# raindrops.net
KiCad netlist of a schematic drawn in EAGLE
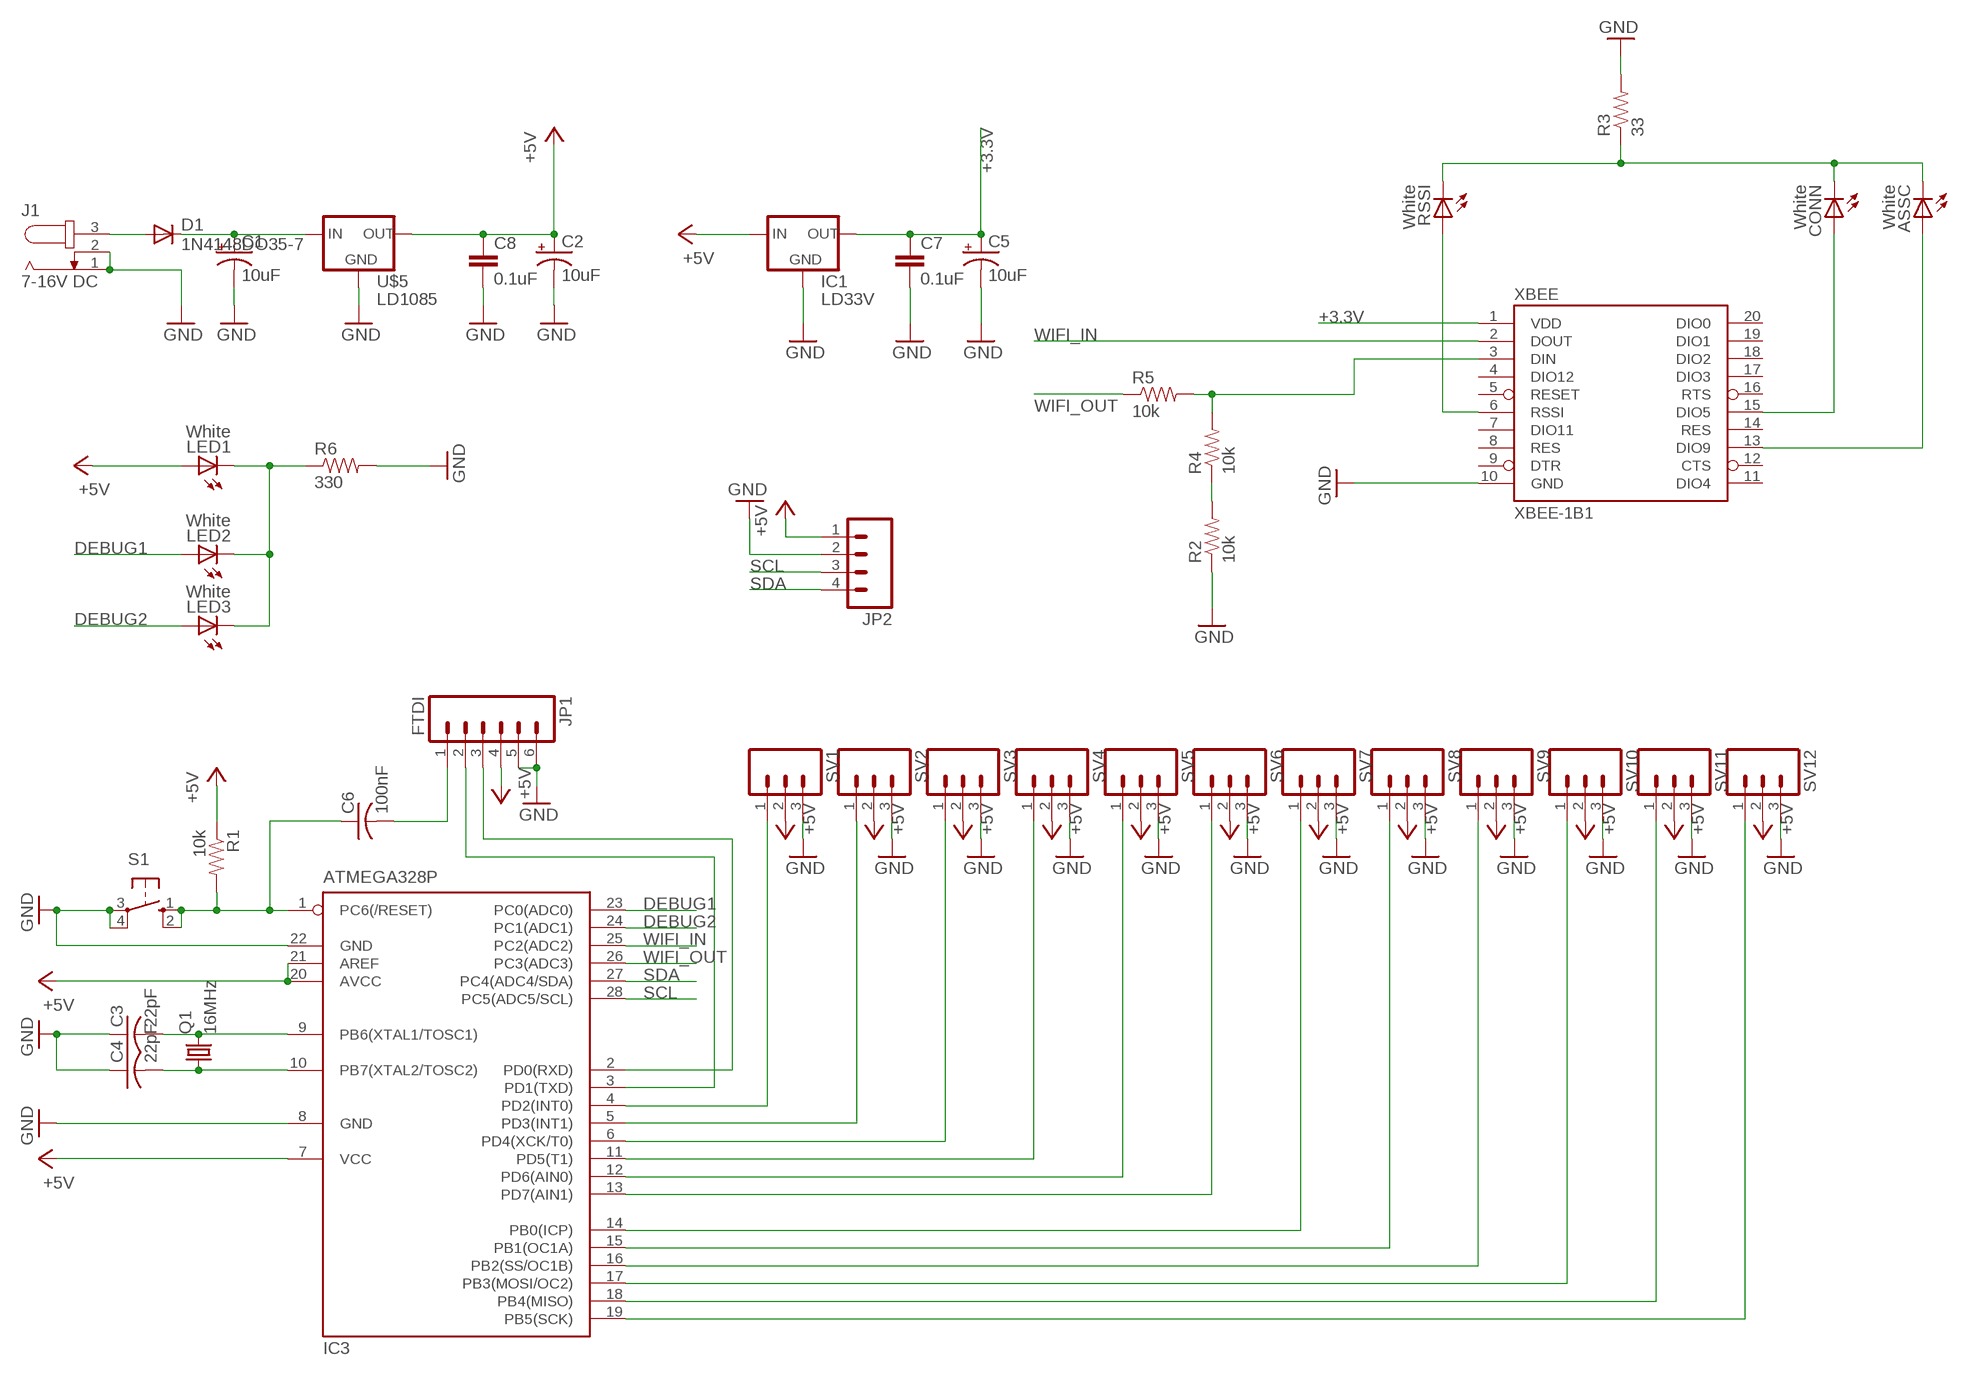
[diagram p0: schematic, sheet 1]

(export (version "E")
  (design (tool "Eeschema 10.0.6"))
  (components
    (comp (ref "ASSC")
      (value "White")
      (footprint "eagle-import:CHIPLED_0603")
      (libsource (lib "eagle-import") (part "LEDCHIPLED_0603"))
    )
    (comp (ref "C1")
      (value "10uF")
      (footprint "eagle-import:CPOL-RADIAL-10UF-25V")
      (libsource (lib "eagle-import") (part "CAP_POLPTH2"))
    )
    (comp (ref "C2")
      (value "10uF")
      (footprint "eagle-import:CPOL-RADIAL-10UF-25V")
      (libsource (lib "eagle-import") (part "CAP_POLPTH2"))
    )
    (comp (ref "C3")
      (value "22pF")
      (footprint "eagle-import:C025-025X050")
      (libsource (lib "eagle-import") (part "C-US025-025X050"))
    )
    (comp (ref "C4")
      (value "22pF")
      (footprint "eagle-import:C025-025X050")
      (libsource (lib "eagle-import") (part "C-US025-025X050"))
    )
    (comp (ref "C5")
      (value "10uF")
      (footprint "eagle-import:CPOL-RADIAL-10UF-25V")
      (libsource (lib "eagle-import") (part "CAP_POLPTH2"))
    )
    (comp (ref "C6")
      (value "100nF")
      (footprint "eagle-import:C025-025X050")
      (libsource (lib "eagle-import") (part "C-US025-025X050"))
    )
    (comp (ref "C7")
      (value "0.1uF")
      (footprint "eagle-import:0402-CAP")
      (libsource (lib "eagle-import") (part ".1UF-CER"))
    )
    (comp (ref "C8")
      (value "0.1uF")
      (footprint "eagle-import:0402-CAP")
      (fields (field (name "PROD_ID") "CAP-00810"))
      (libsource (lib "eagle-import") (part ".1UF-CER"))
    )
    (comp (ref "CONN")
      (value "White")
      (footprint "eagle-import:CHIPLED_0603")
      (libsource (lib "eagle-import") (part "LEDCHIPLED_0603"))
    )
    (comp (ref "D1")
      (value "1N4148DO35-7")
      (footprint "eagle-import:DO35-7")
      (libsource (lib "eagle-import") (part "1N4148DO35-7"))
    )
    (comp (ref "IC1")
      (value "LD33V")
      (footprint "eagle-import:78XXL")
      (libsource (lib "eagle-import") (part "V_REG_LD1117VXX"))
    )
    (comp (ref "IC3")
      (value "ATMEGA328P")
      (footprint "eagle-import:DIL28-3")
      (libsource (lib "eagle-import") (part "MEGA8-P"))
    )
    (comp (ref "J1")
      (value "7-16V DC")
      (footprint "eagle-import:SPC4077")
      (libsource (lib "eagle-import") (part "JACK-PLUG0"))
    )
    (comp (ref "JP1")
      (value "FTDI")
      (footprint "eagle-import:1X06")
      (libsource (lib "eagle-import") (part "M06SIP"))
    )
    (comp (ref "JP2")
      (value "M04PTH")
      (footprint "eagle-import:1X04")
      (libsource (lib "eagle-import") (part "M04PTH"))
    )
    (comp (ref "LED1")
      (value "White")
      (footprint "eagle-import:CHIPLED_0603")
      (libsource (lib "eagle-import") (part "LEDCHIPLED_0603"))
    )
    (comp (ref "LED2")
      (value "White")
      (footprint "eagle-import:CHIPLED_0603")
      (libsource (lib "eagle-import") (part "LEDCHIPLED_0603"))
    )
    (comp (ref "LED3")
      (value "White")
      (footprint "eagle-import:CHIPLED_0603")
      (libsource (lib "eagle-import") (part "LEDCHIPLED_0603"))
    )
    (comp (ref "Q1")
      (value "16MHz")
      (footprint "eagle-import:HC49_S")
      (libsource (lib "eagle-import") (part "CRYSTALHC49S"))
    )
    (comp (ref "R1")
      (value "10k")
      (footprint "eagle-import:0603-RES")
      (libsource (lib "eagle-import") (part "RESISTOR0603-RES"))
    )
    (comp (ref "R2")
      (value "10k")
      (footprint "eagle-import:0603-RES")
      (libsource (lib "eagle-import") (part "RESISTOR0603-RES"))
    )
    (comp (ref "R3")
      (value "33")
      (footprint "eagle-import:AXIAL-0.3")
      (libsource (lib "eagle-import") (part "RESISTORAXIAL-0.3"))
    )
    (comp (ref "R4")
      (value "10k")
      (footprint "eagle-import:0603-RES")
      (libsource (lib "eagle-import") (part "RESISTOR0603-RES"))
    )
    (comp (ref "R5")
      (value "10k")
      (footprint "eagle-import:0603-RES")
      (libsource (lib "eagle-import") (part "RESISTOR0603-RES"))
    )
    (comp (ref "R6")
      (value "330")
      (footprint "eagle-import:AXIAL-0.3")
      (libsource (lib "eagle-import") (part "RESISTORAXIAL-0.3"))
    )
    (comp (ref "RSSI")
      (value "White")
      (footprint "eagle-import:CHIPLED_0603")
      (libsource (lib "eagle-import") (part "LEDCHIPLED_0603"))
    )
    (comp (ref "S1")
      (value "10-XX")
      (footprint "eagle-import:B3F-10XX")
      (fields (field (name "MPN") "B3F-1000"))
      (libsource (lib "eagle-import") (part "10-XX"))
    )
    (comp (ref "SV1")
      (value "M03PTH")
      (footprint "eagle-import:1X03")
      (libsource (lib "eagle-import") (part "M03PTH"))
    )
    (comp (ref "SV2")
      (value "M03PTH")
      (footprint "eagle-import:1X03")
      (libsource (lib "eagle-import") (part "M03PTH"))
    )
    (comp (ref "SV3")
      (value "M03PTH")
      (footprint "eagle-import:1X03")
      (libsource (lib "eagle-import") (part "M03PTH"))
    )
    (comp (ref "SV4")
      (value "M03PTH")
      (footprint "eagle-import:1X03")
      (libsource (lib "eagle-import") (part "M03PTH"))
    )
    (comp (ref "SV5")
      (value "M03PTH")
      (footprint "eagle-import:1X03")
      (libsource (lib "eagle-import") (part "M03PTH"))
    )
    (comp (ref "SV6")
      (value "M03PTH")
      (footprint "eagle-import:1X03")
      (libsource (lib "eagle-import") (part "M03PTH"))
    )
    (comp (ref "SV7")
      (value "M03PTH")
      (footprint "eagle-import:1X03")
      (libsource (lib "eagle-import") (part "M03PTH"))
    )
    (comp (ref "SV8")
      (value "M03PTH")
      (footprint "eagle-import:1X03")
      (libsource (lib "eagle-import") (part "M03PTH"))
    )
    (comp (ref "SV9")
      (value "M03PTH")
      (footprint "eagle-import:1X03")
      (libsource (lib "eagle-import") (part "M03PTH"))
    )
    (comp (ref "SV10")
      (value "M03PTH")
      (footprint "eagle-import:1X03")
      (libsource (lib "eagle-import") (part "M03PTH"))
    )
    (comp (ref "SV11")
      (value "M03PTH")
      (footprint "eagle-import:1X03")
      (libsource (lib "eagle-import") (part "M03PTH"))
    )
    (comp (ref "SV12")
      (value "M03PTH")
      (footprint "eagle-import:1X03")
      (libsource (lib "eagle-import") (part "M03PTH"))
    )
    (comp (ref "U$5")
      (value "LD1085")
      (footprint "eagle-import:78XXL")
      (libsource (lib "eagle-import") (part "V_REG_LD1117VXX"))
    )
    (comp (ref "XBEE")
      (value "XBEE-1B1")
      (footprint "eagle-import:XBEE-1")
      (libsource (lib "eagle-import") (part "XBEE-1B1"))
    )
  )
  (nets
    (net (code "1") (name "+5V") (class "Default")
      (node (ref "C2") (pin "1") (pinfunction "+_1") (pintype "passive"))
      (node (ref "C8") (pin "1") (pinfunction "1_1") (pintype "passive"))
      (node (ref "IC1") (pin "OUT") (pinfunction "IN_OUT") (pintype "input"))
      (node (ref "IC3") (pin "20") (pinfunction "AVCC_20") (pintype "power_in"))
      (node (ref "IC3") (pin "21") (pinfunction "AREF_21") (pintype "passive"))
      (node (ref "IC3") (pin "7") (pinfunction "VCC_7") (pintype "power_in"))
      (node (ref "JP1") (pin "4") (pinfunction "4_4") (pintype "passive"))
      (node (ref "JP2") (pin "1") (pinfunction "1_1") (pintype "passive"))
      (node (ref "LED1") (pin "A") (pinfunction "A_A") (pintype "passive"))
      (node (ref "R1") (pin "1") (pinfunction "1_1") (pintype "passive"))
      (node (ref "SV1") (pin "2") (pinfunction "2_2") (pintype "passive"))
      (node (ref "SV10") (pin "2") (pinfunction "2_2") (pintype "passive"))
      (node (ref "SV11") (pin "2") (pinfunction "2_2") (pintype "passive"))
      (node (ref "SV12") (pin "2") (pinfunction "2_2") (pintype "passive"))
      (node (ref "SV2") (pin "2") (pinfunction "2_2") (pintype "passive"))
      (node (ref "SV3") (pin "2") (pinfunction "2_2") (pintype "passive"))
      (node (ref "SV4") (pin "2") (pinfunction "2_2") (pintype "passive"))
      (node (ref "SV5") (pin "2") (pinfunction "2_2") (pintype "passive"))
      (node (ref "SV6") (pin "2") (pinfunction "2_2") (pintype "passive"))
      (node (ref "SV7") (pin "2") (pinfunction "2_2") (pintype "passive"))
      (node (ref "SV8") (pin "2") (pinfunction "2_2") (pintype "passive"))
      (node (ref "SV9") (pin "2") (pinfunction "2_2") (pintype "passive"))
      (node (ref "U$5") (pin "GND") (pinfunction "OUT_GND") (pintype "output"))
    )
    (net (code "2") (name "/+3.3V") (class "Default")
      (node (ref "C5") (pin "1") (pinfunction "+_1") (pintype "passive"))
      (node (ref "C7") (pin "1") (pinfunction "1_1") (pintype "passive"))
      (node (ref "IC1") (pin "GND") (pinfunction "OUT_GND") (pintype "output"))
      (node (ref "XBEE") (pin "1") (pinfunction "VDD_1") (pintype "power_in"))
    )
    (net (code "3") (name "/DEBUG1") (class "Default")
      (node (ref "IC3") (pin "23") (pinfunction "PC0(ADC0)_23") (pintype "bidirectional"))
      (node (ref "LED2") (pin "A") (pinfunction "A_A") (pintype "passive"))
    )
    (net (code "4") (name "/DEBUG2") (class "Default")
      (node (ref "IC3") (pin "24") (pinfunction "PC1(ADC1)_24") (pintype "bidirectional"))
      (node (ref "LED3") (pin "A") (pinfunction "A_A") (pintype "passive"))
    )
    (net (code "5") (name "/SCL") (class "Default")
      (node (ref "IC3") (pin "28") (pinfunction "PC5(ADC5/SCL)_28") (pintype "bidirectional"))
      (node (ref "JP2") (pin "3") (pinfunction "3_3") (pintype "passive"))
    )
    (net (code "6") (name "/SDA") (class "Default")
      (node (ref "IC3") (pin "27") (pinfunction "PC4(ADC4/SDA)_27") (pintype "bidirectional"))
      (node (ref "JP2") (pin "4") (pinfunction "4_4") (pintype "passive"))
    )
    (net (code "7") (name "/WIFI_IN") (class "Default")
      (node (ref "IC3") (pin "25") (pinfunction "PC2(ADC2)_25") (pintype "bidirectional"))
      (node (ref "XBEE") (pin "2") (pinfunction "DOUT_2") (pintype "output"))
    )
    (net (code "8") (name "/WIFI_OUT") (class "Default")
      (node (ref "IC3") (pin "26") (pinfunction "PC3(ADC3)_26") (pintype "bidirectional"))
      (node (ref "R5") (pin "1") (pinfunction "1_1") (pintype "passive"))
    )
    (net (code "9") (name "GND") (class "Default")
      (node (ref "C1") (pin "2") (pinfunction "-_2") (pintype "passive"))
      (node (ref "C2") (pin "2") (pinfunction "-_2") (pintype "passive"))
      (node (ref "C3") (pin "1") (pinfunction "1_1") (pintype "passive"))
      (node (ref "C4") (pin "1") (pinfunction "1_1") (pintype "passive"))
      (node (ref "C5") (pin "2") (pinfunction "-_2") (pintype "passive"))
      (node (ref "C7") (pin "2") (pinfunction "2_2") (pintype "passive"))
      (node (ref "C8") (pin "2") (pinfunction "2_2") (pintype "passive"))
      (node (ref "IC1") (pin "IN") (pinfunction "GND_IN") (pintype "input"))
      (node (ref "IC3") (pin "22") (pinfunction "GND_22") (pintype "power_in"))
      (node (ref "IC3") (pin "8") (pinfunction "GND_8") (pintype "power_in"))
      (node (ref "J1") (pin "1") (pinfunction "1_1") (pintype "passive"))
      (node (ref "J1") (pin "2") (pinfunction "2_2") (pintype "passive"))
      (node (ref "JP1") (pin "5") (pinfunction "5_5") (pintype "passive"))
      (node (ref "JP1") (pin "6") (pinfunction "6_6") (pintype "passive"))
      (node (ref "JP2") (pin "2") (pinfunction "2_2") (pintype "passive"))
      (node (ref "R2") (pin "1") (pinfunction "1_1") (pintype "passive"))
      (node (ref "R3") (pin "P$2") (pinfunction "2_P$2") (pintype "passive"))
      (node (ref "R6") (pin "P$2") (pinfunction "2_P$2") (pintype "passive"))
      (node (ref "S1") (pin "3") (pinfunction "P_3") (pintype "passive"))
      (node (ref "S1") (pin "4") (pinfunction "P1_4") (pintype "passive"))
      (node (ref "SV1") (pin "3") (pinfunction "3_3") (pintype "passive"))
      (node (ref "SV10") (pin "3") (pinfunction "3_3") (pintype "passive"))
      (node (ref "SV11") (pin "3") (pinfunction "3_3") (pintype "passive"))
      (node (ref "SV12") (pin "3") (pinfunction "3_3") (pintype "passive"))
      (node (ref "SV2") (pin "3") (pinfunction "3_3") (pintype "passive"))
      (node (ref "SV3") (pin "3") (pinfunction "3_3") (pintype "passive"))
      (node (ref "SV4") (pin "3") (pinfunction "3_3") (pintype "passive"))
      (node (ref "SV5") (pin "3") (pinfunction "3_3") (pintype "passive"))
      (node (ref "SV6") (pin "3") (pinfunction "3_3") (pintype "passive"))
      (node (ref "SV7") (pin "3") (pinfunction "3_3") (pintype "passive"))
      (node (ref "SV8") (pin "3") (pinfunction "3_3") (pintype "passive"))
      (node (ref "SV9") (pin "3") (pinfunction "3_3") (pintype "passive"))
      (node (ref "U$5") (pin "IN") (pinfunction "GND_IN") (pintype "input"))
      (node (ref "XBEE") (pin "10") (pinfunction "GND_10") (pintype "power_in"))
    )
    (net (code "10") (name "Net-(C1-+)") (class "Default")
      (node (ref "C1") (pin "1") (pinfunction "+_1") (pintype "passive"))
      (node (ref "D1") (pin "C") (pinfunction "C_C") (pintype "passive"))
      (node (ref "U$5") (pin "OUT") (pinfunction "IN_OUT") (pintype "input"))
    )
    (net (code "11") (name "Net-(C6-Pad2)") (class "Default")
      (node (ref "C6") (pin "2") (pinfunction "2_2") (pintype "passive"))
      (node (ref "JP1") (pin "1") (pinfunction "1_1") (pintype "passive"))
    )
    (net (code "12") (name "Net-(D1-PadA)") (class "Default")
      (node (ref "D1") (pin "A") (pinfunction "A_A") (pintype "passive"))
      (node (ref "J1") (pin "3") (pinfunction "3_3") (pintype "passive"))
    )
    (net (code "13") (name "Net-(IC3-PB0(ICP))") (class "Default")
      (node (ref "IC3") (pin "14") (pinfunction "PB0(ICP)_14") (pintype "bidirectional"))
      (node (ref "SV7") (pin "1") (pinfunction "1_1") (pintype "passive"))
    )
    (net (code "14") (name "Net-(IC3-PB1(OC1A))") (class "Default")
      (node (ref "IC3") (pin "15") (pinfunction "PB1(OC1A)_15") (pintype "bidirectional"))
      (node (ref "SV8") (pin "1") (pinfunction "1_1") (pintype "passive"))
    )
    (net (code "15") (name "Net-(IC3-PB2(SS{slash}OC1B))") (class "Default")
      (node (ref "IC3") (pin "16") (pinfunction "PB2(SS/OC1B)_16") (pintype "bidirectional"))
      (node (ref "SV9") (pin "1") (pinfunction "1_1") (pintype "passive"))
    )
    (net (code "16") (name "Net-(IC3-PB3(MOSI{slash}OC2))") (class "Default")
      (node (ref "IC3") (pin "17") (pinfunction "PB3(MOSI/OC2)_17") (pintype "bidirectional"))
      (node (ref "SV10") (pin "1") (pinfunction "1_1") (pintype "passive"))
    )
    (net (code "17") (name "Net-(IC3-PB4(MISO))") (class "Default")
      (node (ref "IC3") (pin "18") (pinfunction "PB4(MISO)_18") (pintype "bidirectional"))
      (node (ref "SV11") (pin "1") (pinfunction "1_1") (pintype "passive"))
    )
    (net (code "18") (name "Net-(IC3-PB5(SCK))") (class "Default")
      (node (ref "IC3") (pin "19") (pinfunction "PB5(SCK)_19") (pintype "bidirectional"))
      (node (ref "SV12") (pin "1") (pinfunction "1_1") (pintype "passive"))
    )
    (net (code "19") (name "Net-(IC3-PB6(XTAL1{slash}TOSC1))") (class "Default")
      (node (ref "C3") (pin "2") (pinfunction "2_2") (pintype "passive"))
      (node (ref "IC3") (pin "9") (pinfunction "PB6(XTAL1/TOSC1)_9") (pintype "bidirectional"))
      (node (ref "Q1") (pin "2") (pinfunction "2_2") (pintype "passive"))
    )
    (net (code "20") (name "Net-(IC3-PB7(XTAL2{slash}TOSC2))") (class "Default")
      (node (ref "C4") (pin "2") (pinfunction "2_2") (pintype "passive"))
      (node (ref "IC3") (pin "10") (pinfunction "PB7(XTAL2/TOSC2)_10") (pintype "bidirectional"))
      (node (ref "Q1") (pin "1") (pinfunction "1_1") (pintype "passive"))
    )
    (net (code "21") (name "Net-(IC3-PC6({slash}RESET))") (class "Default")
      (node (ref "C6") (pin "1") (pinfunction "1_1") (pintype "passive"))
      (node (ref "IC3") (pin "1") (pinfunction "PC6(/RESET)_1") (pintype "bidirectional"))
      (node (ref "R1") (pin "2") (pinfunction "2_2") (pintype "passive"))
      (node (ref "S1") (pin "1") (pinfunction "S_1") (pintype "passive"))
      (node (ref "S1") (pin "2") (pinfunction "S1_2") (pintype "passive"))
    )
    (net (code "22") (name "Net-(IC3-PD0(RXD))") (class "Default")
      (node (ref "IC3") (pin "2") (pinfunction "PD0(RXD)_2") (pintype "bidirectional"))
      (node (ref "JP1") (pin "3") (pinfunction "3_3") (pintype "passive"))
    )
    (net (code "23") (name "Net-(IC3-PD1(TXD))") (class "Default")
      (node (ref "IC3") (pin "3") (pinfunction "PD1(TXD)_3") (pintype "bidirectional"))
      (node (ref "JP1") (pin "2") (pinfunction "2_2") (pintype "passive"))
    )
    (net (code "24") (name "Net-(IC3-PD2(INT0))") (class "Default")
      (node (ref "IC3") (pin "4") (pinfunction "PD2(INT0)_4") (pintype "bidirectional"))
      (node (ref "SV1") (pin "1") (pinfunction "1_1") (pintype "passive"))
    )
    (net (code "25") (name "Net-(IC3-PD3(INT1))") (class "Default")
      (node (ref "IC3") (pin "5") (pinfunction "PD3(INT1)_5") (pintype "bidirectional"))
      (node (ref "SV2") (pin "1") (pinfunction "1_1") (pintype "passive"))
    )
    (net (code "26") (name "Net-(IC3-PD4(XCK{slash}T0))") (class "Default")
      (node (ref "IC3") (pin "6") (pinfunction "PD4(XCK/T0)_6") (pintype "bidirectional"))
      (node (ref "SV3") (pin "1") (pinfunction "1_1") (pintype "passive"))
    )
    (net (code "27") (name "Net-(IC3-PD5(T1))") (class "Default")
      (node (ref "IC3") (pin "11") (pinfunction "PD5(T1)_11") (pintype "bidirectional"))
      (node (ref "SV4") (pin "1") (pinfunction "1_1") (pintype "passive"))
    )
    (net (code "28") (name "Net-(IC3-PD6(AIN0))") (class "Default")
      (node (ref "IC3") (pin "12") (pinfunction "PD6(AIN0)_12") (pintype "bidirectional"))
      (node (ref "SV5") (pin "1") (pinfunction "1_1") (pintype "passive"))
    )
    (net (code "29") (name "Net-(IC3-PD7(AIN1))") (class "Default")
      (node (ref "IC3") (pin "13") (pinfunction "PD7(AIN1)_13") (pintype "bidirectional"))
      (node (ref "SV6") (pin "1") (pinfunction "1_1") (pintype "passive"))
    )
    (net (code "30") (name "Net-(R2-Pad2)") (class "Default")
      (node (ref "R2") (pin "2") (pinfunction "2_2") (pintype "passive"))
      (node (ref "R4") (pin "1") (pinfunction "1_1") (pintype "passive"))
    )
    (net (code "31") (name "Net-(R3-1)") (class "Default")
      (node (ref "ASSC") (pin "C") (pinfunction "C_C") (pintype "passive"))
      (node (ref "CONN") (pin "C") (pinfunction "C_C") (pintype "passive"))
      (node (ref "R3") (pin "P$1") (pinfunction "1_P$1") (pintype "passive"))
      (node (ref "RSSI") (pin "C") (pinfunction "C_C") (pintype "passive"))
    )
    (net (code "32") (name "Net-(R6-1)") (class "Default")
      (node (ref "LED1") (pin "C") (pinfunction "C_C") (pintype "passive"))
      (node (ref "LED2") (pin "C") (pinfunction "C_C") (pintype "passive"))
      (node (ref "LED3") (pin "C") (pinfunction "C_C") (pintype "passive"))
      (node (ref "R6") (pin "P$1") (pinfunction "1_P$1") (pintype "passive"))
    )
    (net (code "33") (name "Net-(XBEE-DIN)") (class "Default")
      (node (ref "R4") (pin "2") (pinfunction "2_2") (pintype "passive"))
      (node (ref "R5") (pin "2") (pinfunction "2_2") (pintype "passive"))
      (node (ref "XBEE") (pin "3") (pinfunction "DIN_3") (pintype "input"))
    )
    (net (code "34") (name "Net-(XBEE-DIO5)") (class "Default")
      (node (ref "CONN") (pin "A") (pinfunction "A_A") (pintype "passive"))
      (node (ref "XBEE") (pin "15") (pinfunction "DIO5_15") (pintype "bidirectional"))
    )
    (net (code "35") (name "Net-(XBEE-DIO9)") (class "Default")
      (node (ref "ASSC") (pin "A") (pinfunction "A_A") (pintype "passive"))
      (node (ref "XBEE") (pin "13") (pinfunction "DIO9_13") (pintype "bidirectional"))
    )
    (net (code "36") (name "Net-(XBEE-RSSI)") (class "Default")
      (node (ref "RSSI") (pin "A") (pinfunction "A_A") (pintype "passive"))
      (node (ref "XBEE") (pin "6") (pinfunction "RSSI_6") (pintype "bidirectional"))
    )
    (net (code "37") (name "unconnected-(XBEE-CTS-Pad12)") (class "Default")
      (node (ref "XBEE") (pin "12") (pinfunction "CTS_12") (pintype "output"))
    )
    (net (code "38") (name "unconnected-(XBEE-DIO0-Pad20)") (class "Default")
      (node (ref "XBEE") (pin "20") (pinfunction "DIO0_20") (pintype "bidirectional"))
    )
    (net (code "39") (name "unconnected-(XBEE-DIO1-Pad19)") (class "Default")
      (node (ref "XBEE") (pin "19") (pinfunction "DIO1_19") (pintype "bidirectional"))
    )
    (net (code "40") (name "unconnected-(XBEE-DIO2-Pad18)") (class "Default")
      (node (ref "XBEE") (pin "18") (pinfunction "DIO2_18") (pintype "bidirectional"))
    )
    (net (code "41") (name "unconnected-(XBEE-DIO3-Pad17)") (class "Default")
      (node (ref "XBEE") (pin "17") (pinfunction "DIO3_17") (pintype "bidirectional"))
    )
    (net (code "42") (name "unconnected-(XBEE-DIO4-Pad11)") (class "Default")
      (node (ref "XBEE") (pin "11") (pinfunction "DIO4_11") (pintype "bidirectional"))
    )
    (net (code "43") (name "unconnected-(XBEE-DIO11-Pad7)") (class "Default")
      (node (ref "XBEE") (pin "7") (pinfunction "DIO11_7") (pintype "bidirectional"))
    )
    (net (code "44") (name "unconnected-(XBEE-DIO12-Pad4)") (class "Default")
      (node (ref "XBEE") (pin "4") (pinfunction "DIO12_4") (pintype "bidirectional"))
    )
    (net (code "45") (name "unconnected-(XBEE-DTR-Pad9)") (class "Default")
      (node (ref "XBEE") (pin "9") (pinfunction "DTR_9") (pintype "bidirectional"))
    )
    (net (code "46") (name "unconnected-(XBEE-RES-Pad8)") (class "Default")
      (node (ref "XBEE") (pin "8") (pinfunction "RES_8") (pintype "bidirectional"))
    )
    (net (code "47") (name "unconnected-(XBEE-RES-Pad14)") (class "Default")
      (node (ref "XBEE") (pin "14") (pinfunction "RES_14") (pintype "bidirectional"))
    )
    (net (code "48") (name "unconnected-(XBEE-RESET-Pad5)") (class "Default")
      (node (ref "XBEE") (pin "5") (pinfunction "RESET_5") (pintype "input"))
    )
    (net (code "49") (name "unconnected-(XBEE-RTS-Pad16)") (class "Default")
      (node (ref "XBEE") (pin "16") (pinfunction "RTS_16") (pintype "input"))
    )
  )
)
